# SCH_LucesLectura_2023-04-08.net
KiCad netlist of a schematic drawn in EasyEDA
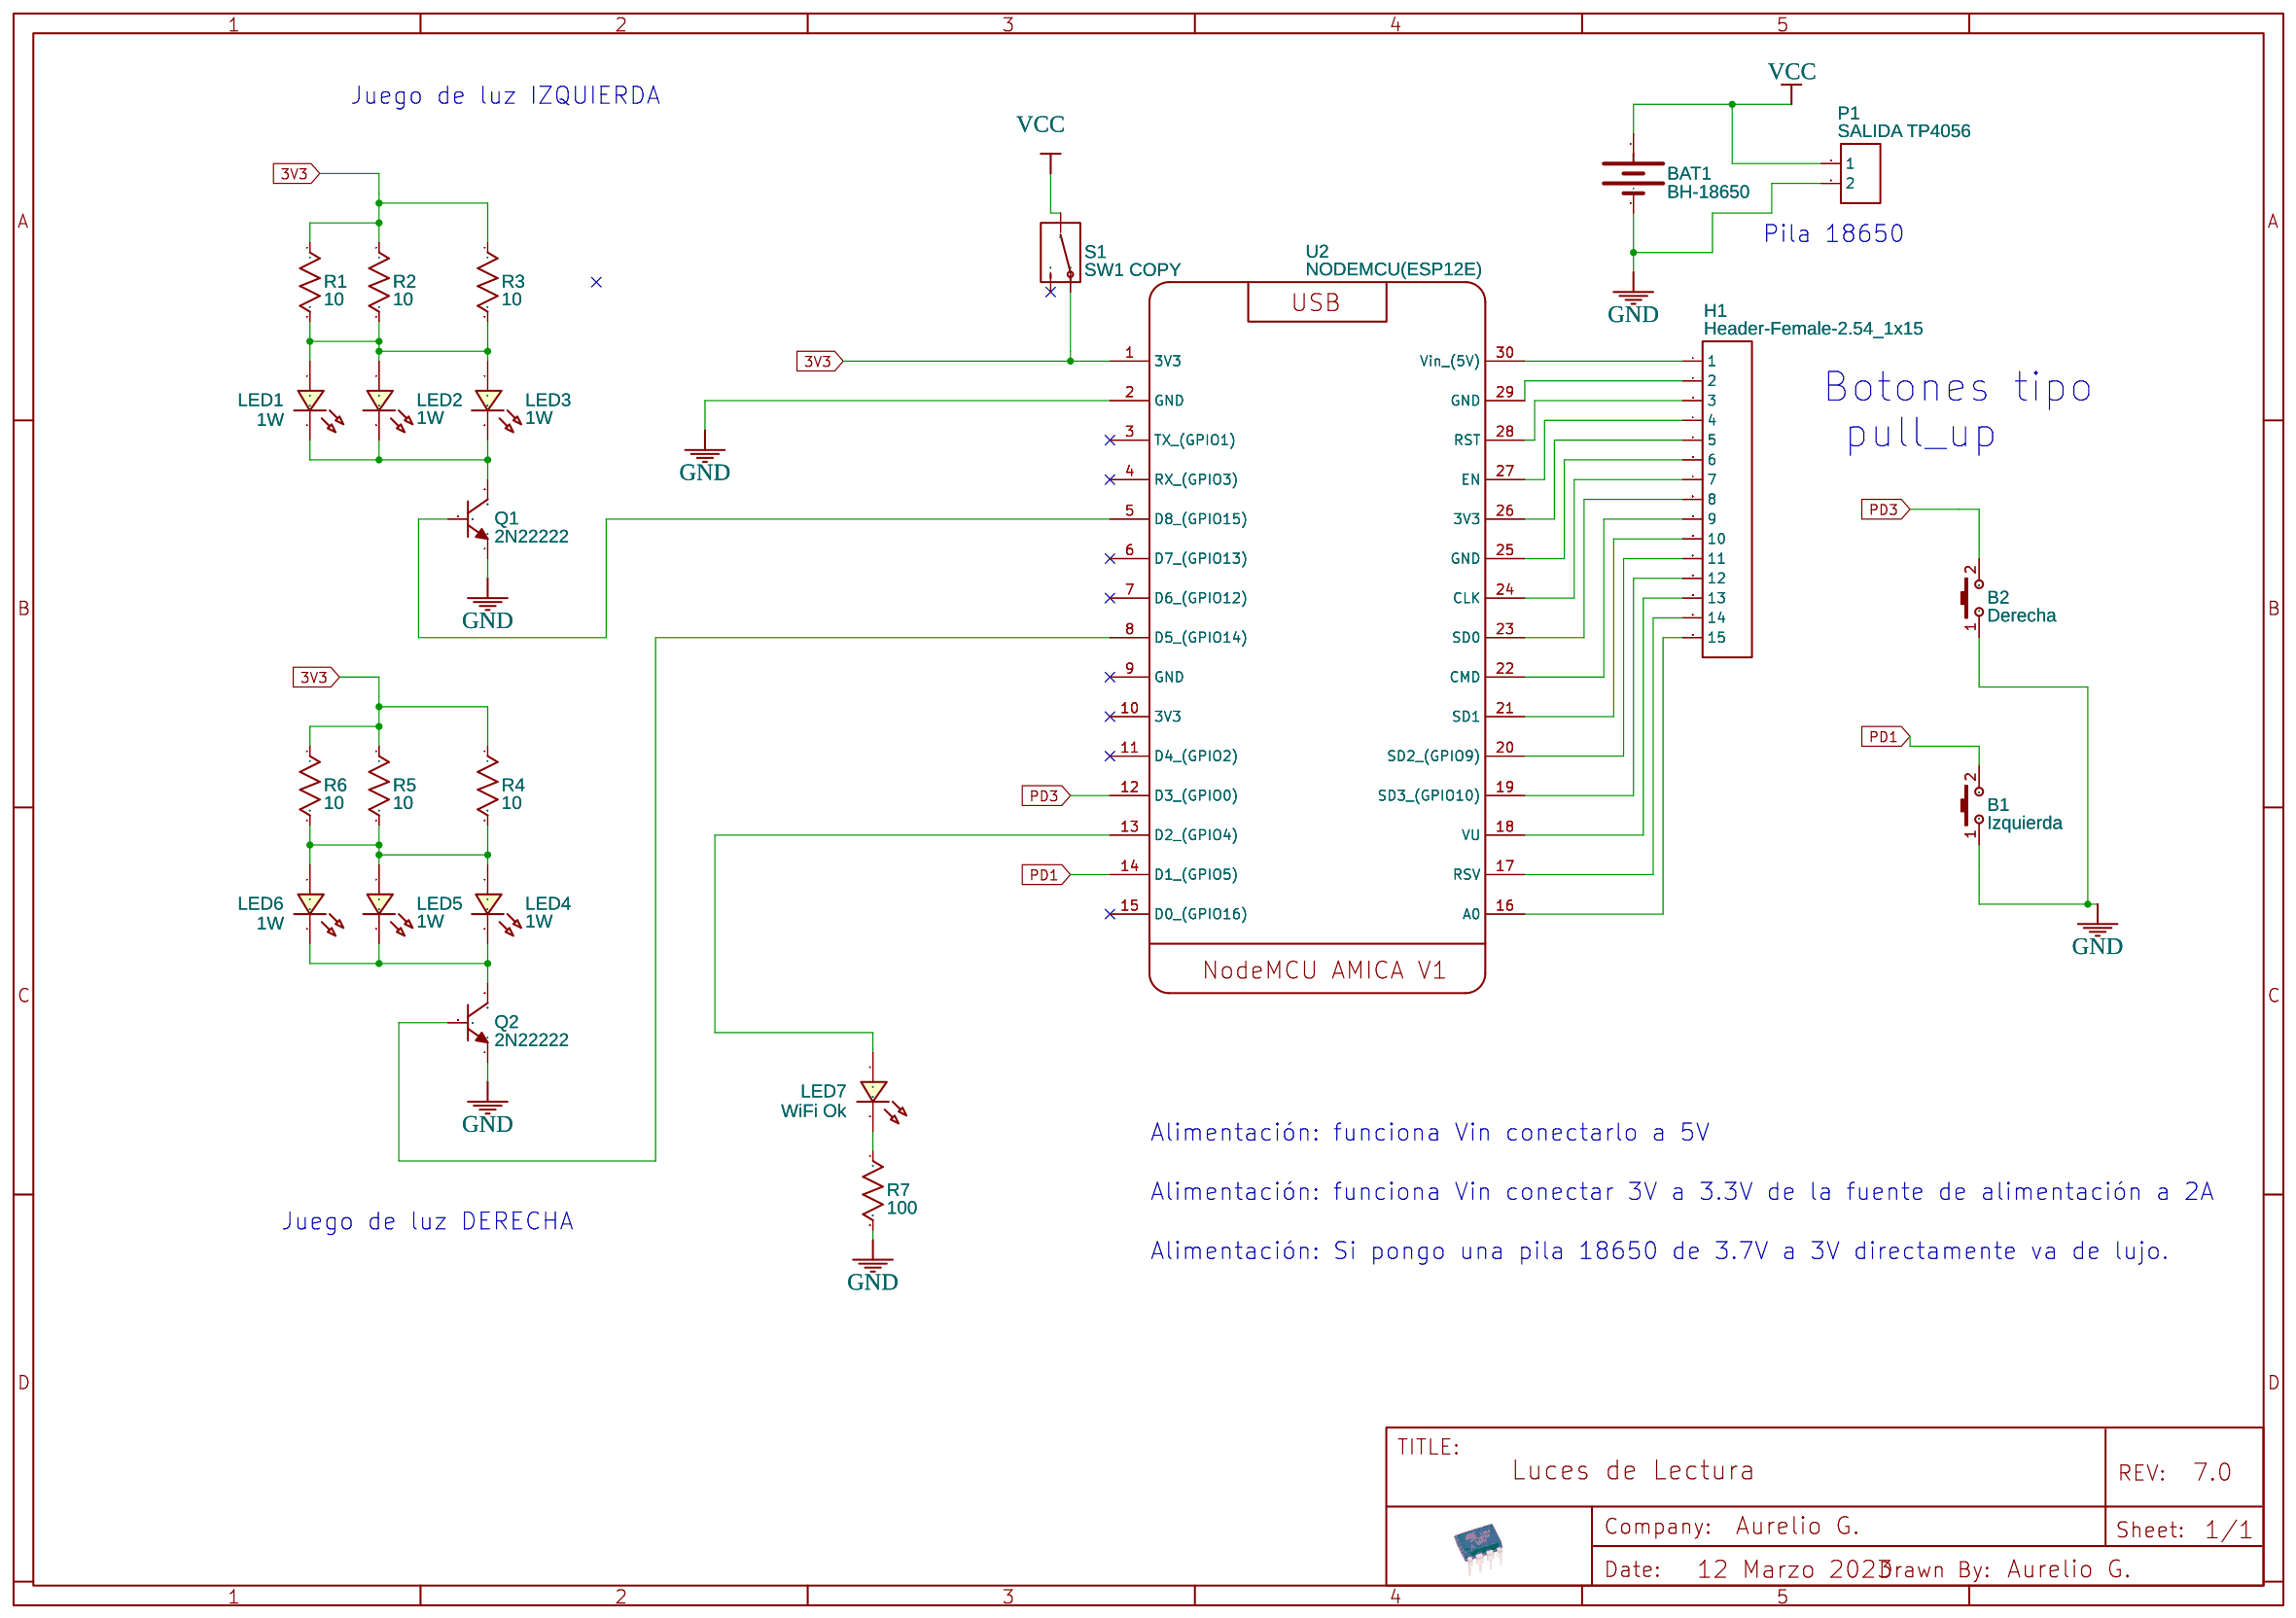
[diagram p0: schematic sheet]

(export (version "E")
  (design (tool "Eeschema 10.0.6"))
  (components
    (comp (ref "B1")
      (value "Izquierda")
      (fields (field (name "BOM_Manufacturer Part") "PUSH_BUTTON_2Pini"))
      (libsource (lib "") (part "push_button_2pins"))
    )
    (comp (ref "B2")
      (value "Derecha")
      (fields (field (name "BOM_Manufacturer Part") "PUSH_BUTTON_2Pini"))
      (libsource (lib "") (part "push_button_2pins"))
    )
    (comp (ref "BAT1")
      (value "BH-18650")
      (fields (field (name "BOM_Supplier Part") "C9900017971"))
      (libsource (lib "") (part "BH-18650"))
    )
    (comp (ref "H1")
      (value "Header-Female-2.54_1x15")
      (fields
        (field (name "BOM_Manufacturer Part") "B-2200S15P-A120")
        (field (name "BOM_Supplier Part") "C124408")
      )
      (libsource (lib "") (part "Header-Female-2.54_1x15"))
    )
    (comp (ref "LED1")
      (value "1W")
      (fields
        (field (name "BOM_Manufacturer Part") "19-217/R6C-AL1M2VY/3T")
        (field (name "BOM_Supplier Part") "C72044")
      )
      (libsource (lib "") (part "LED-0603_R"))
    )
    (comp (ref "LED2")
      (value "1W")
      (fields
        (field (name "BOM_Manufacturer Part") "19-217/R6C-AL1M2VY/3T")
        (field (name "BOM_Supplier Part") "C72044")
      )
      (libsource (lib "") (part "LED-0603_R"))
    )
    (comp (ref "LED3")
      (value "1W")
      (fields
        (field (name "BOM_Manufacturer Part") "19-217/R6C-AL1M2VY/3T")
        (field (name "BOM_Supplier Part") "C72044")
      )
      (libsource (lib "") (part "LED-0603_R"))
    )
    (comp (ref "LED4")
      (value "1W")
      (fields
        (field (name "BOM_Manufacturer Part") "19-217/R6C-AL1M2VY/3T")
        (field (name "BOM_Supplier Part") "C72044")
      )
      (libsource (lib "") (part "LED-0603_R"))
    )
    (comp (ref "LED5")
      (value "1W")
      (fields
        (field (name "BOM_Manufacturer Part") "19-217/R6C-AL1M2VY/3T")
        (field (name "BOM_Supplier Part") "C72044")
      )
      (libsource (lib "") (part "LED-0603_R"))
    )
    (comp (ref "LED6")
      (value "1W")
      (fields
        (field (name "BOM_Manufacturer Part") "19-217/R6C-AL1M2VY/3T")
        (field (name "BOM_Supplier Part") "C72044")
      )
      (libsource (lib "") (part "LED-0603_R"))
    )
    (comp (ref "LED7")
      (value "WiFi Ok")
      (fields
        (field (name "BOM_Manufacturer Part") "19-217/R6C-AL1M2VY/3T")
        (field (name "BOM_Supplier Part") "C72044")
      )
      (libsource (lib "") (part "LED-0603_R"))
    )
    (comp (ref "P1") (value "SALIDA TP4056") (libsource (lib "") (part "CONN-TH_2P-P5.00")))
    (comp (ref "Q1")
      (value "2N22222")
      (fields (field (name "BOM_Manufacturer Part") "2N3904") (field (name "BOM_Supplier Part") "C118538"))
      (libsource (lib "") (part "Transistor.2N22222.NPN"))
    )
    (comp (ref "Q2")
      (value "2N22222")
      (fields (field (name "BOM_Manufacturer Part") "2N3904") (field (name "BOM_Supplier Part") "C118538"))
      (libsource (lib "") (part "Transistor.2N22222.NPN"))
    )
    (comp (ref "R1") (value "10") (libsource (lib "") (part "R_0603_US")))
    (comp (ref "R2") (value "10") (libsource (lib "") (part "R_0603_US")))
    (comp (ref "R3") (value "10") (libsource (lib "") (part "R_0603_US")))
    (comp (ref "R4") (value "10") (libsource (lib "") (part "R_0603_US")))
    (comp (ref "R5") (value "10") (libsource (lib "") (part "R_0603_US")))
    (comp (ref "R6") (value "10") (libsource (lib "") (part "R_0603_US")))
    (comp (ref "R7") (value "100") (libsource (lib "") (part "R_0603_US")))
    (comp (ref "S1") (value "SW1 COPY") (libsource (lib "") (part "SW1 COPY")))
    (comp (ref "U2")
      (value "NODEMCU(ESP12E)")
      (fields (field (name "BOM_Supplier Part") "nodemcu-v2"))
      (libsource (lib "") (part "NODEMCU(ESP12E)"))
    )
  )
  (nets
    (net (code "1") (name "3V3") (class "Default")
      (node (ref "R1") (pin "1") (pinfunction "1_1") (pintype "unspecified"))
      (node (ref "R2") (pin "1") (pinfunction "1_1") (pintype "unspecified"))
      (node (ref "R3") (pin "1") (pinfunction "1_1") (pintype "unspecified"))
      (node (ref "R4") (pin "1") (pinfunction "1_1") (pintype "unspecified"))
      (node (ref "R5") (pin "1") (pinfunction "1_1") (pintype "unspecified"))
      (node (ref "R6") (pin "1") (pinfunction "1_1") (pintype "unspecified"))
      (node (ref "S1") (pin "1") (pinfunction "O_1") (pintype "bidirectional"))
      (node (ref "U2") (pin "1") (pinfunction "3V3_1") (pintype "unspecified"))
    )
    (net (code "2") (name "GND") (class "Default")
      (node (ref "B1") (pin "1") (pinfunction "1_1") (pintype "unspecified"))
      (node (ref "B2") (pin "1") (pinfunction "1_1") (pintype "unspecified"))
      (node (ref "BAT1") (pin "2") (pinfunction "+_2") (pintype "passive"))
      (node (ref "P1") (pin "2") (pinfunction "2_2") (pintype "unspecified"))
      (node (ref "Q1") (pin "1") (pinfunction "E_1") (pintype "unspecified"))
      (node (ref "Q2") (pin "1") (pinfunction "E_1") (pintype "unspecified"))
      (node (ref "R7") (pin "2") (pinfunction "2_2") (pintype "unspecified"))
      (node (ref "U2") (pin "2") (pinfunction "GND_2") (pintype "unspecified"))
    )
    (net (code "3") (name "Net-(H1-Pad2)") (class "Default")
      (node (ref "H1") (pin "2") (pinfunction "2_2") (pintype "unspecified"))
      (node (ref "U2") (pin "29") (pinfunction "GND_29") (pintype "unspecified"))
    )
    (net (code "4") (name "Net-(H1-Pad5)") (class "Default")
      (node (ref "H1") (pin "5") (pinfunction "5_5") (pintype "unspecified"))
      (node (ref "U2") (pin "26") (pinfunction "3V3_26") (pintype "unspecified"))
    )
    (net (code "5") (name "Net-(H1-Pad6)") (class "Default")
      (node (ref "H1") (pin "6") (pinfunction "6_6") (pintype "unspecified"))
      (node (ref "U2") (pin "25") (pinfunction "GND_25") (pintype "unspecified"))
    )
    (net (code "6") (name "Net-(LED1-Pad1)") (class "Default")
      (node (ref "LED1") (pin "1") (pinfunction "1_1") (pintype "unspecified"))
      (node (ref "LED2") (pin "1") (pinfunction "1_1") (pintype "unspecified"))
      (node (ref "LED3") (pin "1") (pinfunction "1_1") (pintype "unspecified"))
      (node (ref "R1") (pin "2") (pinfunction "2_2") (pintype "unspecified"))
      (node (ref "R2") (pin "2") (pinfunction "2_2") (pintype "unspecified"))
      (node (ref "R3") (pin "2") (pinfunction "2_2") (pintype "unspecified"))
    )
    (net (code "7") (name "Net-(LED4-Pad1)") (class "Default")
      (node (ref "LED4") (pin "1") (pinfunction "1_1") (pintype "unspecified"))
      (node (ref "LED5") (pin "1") (pinfunction "1_1") (pintype "unspecified"))
      (node (ref "LED6") (pin "1") (pinfunction "1_1") (pintype "unspecified"))
      (node (ref "R4") (pin "2") (pinfunction "2_2") (pintype "unspecified"))
      (node (ref "R5") (pin "2") (pinfunction "2_2") (pintype "unspecified"))
      (node (ref "R6") (pin "2") (pinfunction "2_2") (pintype "unspecified"))
    )
    (net (code "8") (name "Net-(LED7-Pad2)") (class "Default")
      (node (ref "LED7") (pin "2") (pinfunction "2_2") (pintype "unspecified"))
      (node (ref "R7") (pin "1") (pinfunction "1_1") (pintype "unspecified"))
    )
    (net (code "9") (name "Net-(Q1-B)") (class "Default")
      (node (ref "Q1") (pin "2") (pinfunction "B_2") (pintype "unspecified"))
      (node (ref "U2") (pin "5") (pinfunction "D8_(GPIO15)_5") (pintype "unspecified"))
    )
    (net (code "10") (name "Net-(Q1-C)") (class "Default")
      (node (ref "LED1") (pin "2") (pinfunction "2_2") (pintype "unspecified"))
      (node (ref "LED2") (pin "2") (pinfunction "2_2") (pintype "unspecified"))
      (node (ref "LED3") (pin "2") (pinfunction "2_2") (pintype "unspecified"))
      (node (ref "Q1") (pin "3") (pinfunction "C_3") (pintype "unspecified"))
    )
    (net (code "11") (name "Net-(Q2-B)") (class "Default")
      (node (ref "Q2") (pin "2") (pinfunction "B_2") (pintype "unspecified"))
      (node (ref "U2") (pin "8") (pinfunction "D5_(GPIO14)_8") (pintype "unspecified"))
    )
    (net (code "12") (name "Net-(Q2-C)") (class "Default")
      (node (ref "LED4") (pin "2") (pinfunction "2_2") (pintype "unspecified"))
      (node (ref "LED5") (pin "2") (pinfunction "2_2") (pintype "unspecified"))
      (node (ref "LED6") (pin "2") (pinfunction "2_2") (pintype "unspecified"))
      (node (ref "Q2") (pin "3") (pinfunction "C_3") (pintype "unspecified"))
    )
    (net (code "13") (name "Net-(U2-A0)") (class "Default")
      (node (ref "H1") (pin "15") (pinfunction "15_15") (pintype "unspecified"))
      (node (ref "U2") (pin "16") (pinfunction "A0_16") (pintype "unspecified"))
    )
    (net (code "14") (name "Net-(U2-CLK)") (class "Default")
      (node (ref "H1") (pin "7") (pinfunction "7_7") (pintype "unspecified"))
      (node (ref "U2") (pin "24") (pinfunction "CLK_24") (pintype "unspecified"))
    )
    (net (code "15") (name "Net-(U2-CMD)") (class "Default")
      (node (ref "H1") (pin "9") (pinfunction "9_9") (pintype "unspecified"))
      (node (ref "U2") (pin "22") (pinfunction "CMD_22") (pintype "unspecified"))
    )
    (net (code "16") (name "Net-(U2-D2_(GPIO4))") (class "Default")
      (node (ref "LED7") (pin "1") (pinfunction "1_1") (pintype "unspecified"))
      (node (ref "U2") (pin "13") (pinfunction "D2_(GPIO4)_13") (pintype "unspecified"))
    )
    (net (code "17") (name "Net-(U2-EN)") (class "Default")
      (node (ref "H1") (pin "4") (pinfunction "4_4") (pintype "unspecified"))
      (node (ref "U2") (pin "27") (pinfunction "EN_27") (pintype "unspecified"))
    )
    (net (code "18") (name "Net-(U2-RST)") (class "Default")
      (node (ref "H1") (pin "3") (pinfunction "3_3") (pintype "unspecified"))
      (node (ref "U2") (pin "28") (pinfunction "RST_28") (pintype "unspecified"))
    )
    (net (code "19") (name "Net-(U2-RSV)") (class "Default")
      (node (ref "H1") (pin "14") (pinfunction "14_14") (pintype "unspecified"))
      (node (ref "U2") (pin "17") (pinfunction "RSV_17") (pintype "unspecified"))
    )
    (net (code "20") (name "Net-(U2-SD0)") (class "Default")
      (node (ref "H1") (pin "8") (pinfunction "8_8") (pintype "unspecified"))
      (node (ref "U2") (pin "23") (pinfunction "SD0_23") (pintype "unspecified"))
    )
    (net (code "21") (name "Net-(U2-SD1)") (class "Default")
      (node (ref "H1") (pin "10") (pinfunction "10_10") (pintype "unspecified"))
      (node (ref "U2") (pin "21") (pinfunction "SD1_21") (pintype "unspecified"))
    )
    (net (code "22") (name "Net-(U2-SD2_(GPIO9))") (class "Default")
      (node (ref "H1") (pin "11") (pinfunction "11_11") (pintype "unspecified"))
      (node (ref "U2") (pin "20") (pinfunction "SD2_(GPIO9)_20") (pintype "unspecified"))
    )
    (net (code "23") (name "Net-(U2-SD3_(GPIO10))") (class "Default")
      (node (ref "H1") (pin "12") (pinfunction "12_12") (pintype "unspecified"))
      (node (ref "U2") (pin "19") (pinfunction "SD3_(GPIO10)_19") (pintype "unspecified"))
    )
    (net (code "24") (name "Net-(U2-VU)") (class "Default")
      (node (ref "H1") (pin "13") (pinfunction "13_13") (pintype "unspecified"))
      (node (ref "U2") (pin "18") (pinfunction "VU_18") (pintype "unspecified"))
    )
    (net (code "25") (name "Net-(U2-Vin_(5V))") (class "Default")
      (node (ref "H1") (pin "1") (pinfunction "1_1") (pintype "unspecified"))
      (node (ref "U2") (pin "30") (pinfunction "Vin_(5V)_30") (pintype "unspecified"))
    )
    (net (code "26") (name "PD1") (class "Default")
      (node (ref "B1") (pin "2") (pinfunction "2_2") (pintype "unspecified"))
      (node (ref "U2") (pin "14") (pinfunction "D1_(GPIO5)_14") (pintype "unspecified"))
    )
    (net (code "27") (name "PD3") (class "Default")
      (node (ref "B2") (pin "2") (pinfunction "2_2") (pintype "unspecified"))
      (node (ref "U2") (pin "12") (pinfunction "D3_(GPIO0)_12") (pintype "unspecified"))
    )
    (net (code "28") (name "VCC") (class "Default")
      (node (ref "BAT1") (pin "1") (pinfunction "-_1") (pintype "passive"))
      (node (ref "P1") (pin "1") (pinfunction "1_1") (pintype "unspecified"))
      (node (ref "S1") (pin "2") (pinfunction "P_2") (pintype "bidirectional"))
    )
    (net (code "29") (name "unconnected-(S1-S-Pad3)") (class "Default")
      (node (ref "S1") (pin "3") (pinfunction "S_3") (pintype "bidirectional+no_connect"))
    )
    (net (code "30") (name "unconnected-(U2-3V3-Pad10)") (class "Default")
      (node (ref "U2") (pin "10") (pinfunction "3V3_10") (pintype "unspecified+no_connect"))
    )
    (net (code "31") (name "unconnected-(U2-D0_(GPIO16)-Pad15)") (class "Default")
      (node (ref "U2") (pin "15") (pinfunction "D0_(GPIO16)_15") (pintype "unspecified+no_connect"))
    )
    (net (code "32") (name "unconnected-(U2-D4_(GPIO2)-Pad11)") (class "Default")
      (node (ref "U2") (pin "11") (pinfunction "D4_(GPIO2)_11") (pintype "unspecified+no_connect"))
    )
    (net (code "33") (name "unconnected-(U2-D6_(GPIO12)-Pad7)") (class "Default")
      (node (ref "U2") (pin "7") (pinfunction "D6_(GPIO12)_7") (pintype "unspecified+no_connect"))
    )
    (net (code "34") (name "unconnected-(U2-D7_(GPIO13)-Pad6)") (class "Default")
      (node (ref "U2") (pin "6") (pinfunction "D7_(GPIO13)_6") (pintype "unspecified+no_connect"))
    )
    (net (code "35") (name "unconnected-(U2-GND-Pad9)") (class "Default")
      (node (ref "U2") (pin "9") (pinfunction "GND_9") (pintype "unspecified+no_connect"))
    )
    (net (code "36") (name "unconnected-(U2-RX_(GPIO3)-Pad4)") (class "Default")
      (node (ref "U2") (pin "4") (pinfunction "RX_(GPIO3)_4") (pintype "unspecified+no_connect"))
    )
    (net (code "37") (name "unconnected-(U2-TX_(GPIO1)-Pad3)") (class "Default")
      (node (ref "U2") (pin "3") (pinfunction "TX_(GPIO1)_3") (pintype "unspecified+no_connect"))
    )
  )
)
